# NAVIGATION_UNIT.net
KiCad netlist of a schematic drawn in Altium Designer
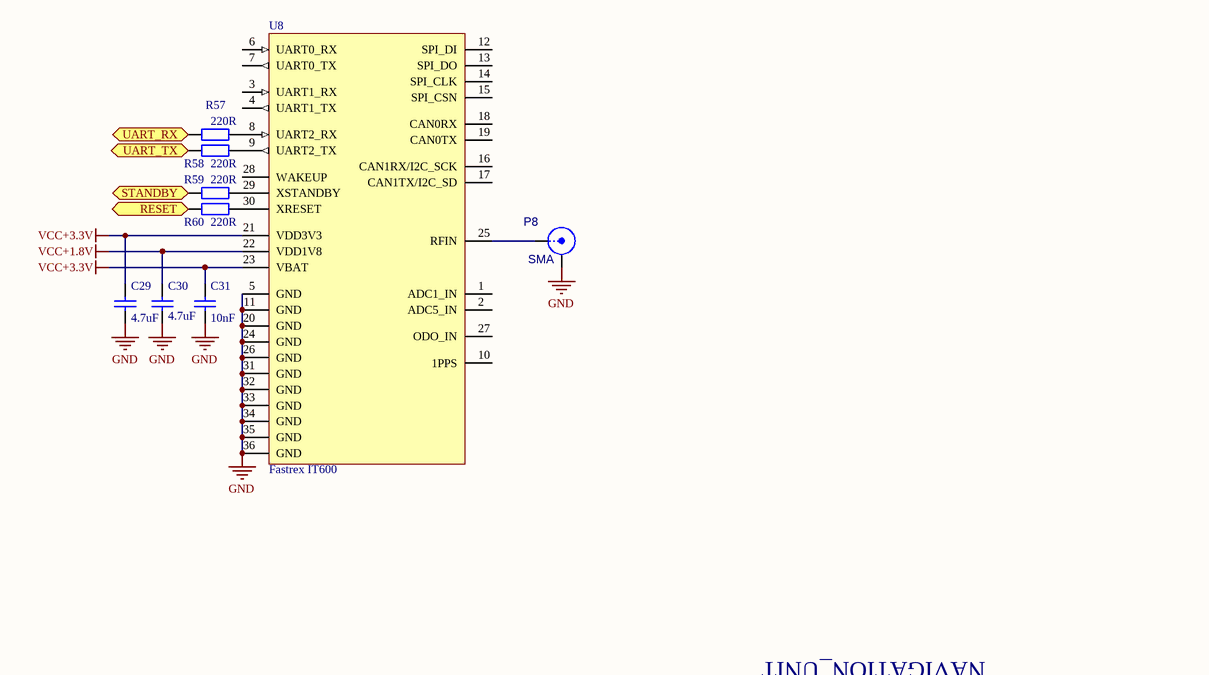
[diagram p0: NAVIGATION_UNIT.SchDoc]

(export (version "E")
  (design (tool "Eeschema 10.0.6"))
  (components
    (comp (ref "C29")
      (value "4.7uF")
      (footprint "C0805")
      (description "Capasitor_SMD_0808/")
      (fields (field (name "Comment") "0805"))
      (libsource (lib "NEW") (part "Capasitor_SMD_0805"))
    )
    (comp (ref "C30")
      (value "4.7uF")
      (footprint "C0805")
      (description "Capasitor_SMD_0808/")
      (fields (field (name "Comment") "0805"))
      (libsource (lib "NEW") (part "Capasitor_SMD_0805"))
    )
    (comp (ref "C31")
      (value "10nF")
      (footprint "C0603")
      (description "Capasitor_SMD_0808/")
      (fields (field (name "Comment") "0805"))
      (libsource (lib "NEW") (part "Capasitor_SMD_0805"))
    )
    (comp (ref "P8")
      (value "SMA")
      (footprint "SMA")
      (fields (field (name "PUBLISHER") "Altium Limited"))
      (libsource (lib "NEW") (part "SMA"))
    )
    (comp (ref "R57")
      (value "220R")
      (footprint "C0603")
      (description "Resistor")
      (fields (field (name "Comment") "RES"))
      (libsource (lib "NEW") (part "RES"))
    )
    (comp (ref "R58")
      (value "220R")
      (footprint "C0603")
      (description "Resistor")
      (fields (field (name "Comment") "RES"))
      (libsource (lib "NEW") (part "RES"))
    )
    (comp (ref "R59")
      (value "220R")
      (footprint "C0603")
      (description "Resistor")
      (fields (field (name "Comment") "RES"))
      (libsource (lib "NEW") (part "RES"))
    )
    (comp (ref "R60")
      (value "220R")
      (footprint "C0603")
      (description "Resistor")
      (fields (field (name "Comment") "RES"))
      (libsource (lib "NEW") (part "RES"))
    )
    (comp (ref "U8")
      (value "Fastrex IT600")
      (footprint "Fastrex_IT600")
      (description "GPS/ГЛОНАСС")
      (libsource (lib "NEW") (part "Fastrax IT600"))
    )
  )
  (nets
    (net (code "1") (name "/RESET") (class "Default")
      (node (ref "R60") (pin "1") (pinfunction "1_1") (pintype "passive"))
    )
    (net (code "2") (name "/STANDBY") (class "Default")
      (node (ref "R59") (pin "1") (pinfunction "1_1") (pintype "passive"))
    )
    (net (code "3") (name "/UART_RX") (class "Default")
      (node (ref "R57") (pin "1") (pinfunction "1_1") (pintype "passive"))
    )
    (net (code "4") (name "/UART_TX") (class "Default")
      (node (ref "R58") (pin "1") (pinfunction "1_1") (pintype "passive"))
    )
    (net (code "5") (name "GND") (class "Default")
      (node (ref "C29") (pin "2") (pinfunction "2_2") (pintype "passive"))
      (node (ref "C30") (pin "2") (pinfunction "2_2") (pintype "passive"))
      (node (ref "C31") (pin "2") (pinfunction "2_2") (pintype "passive"))
      (node (ref "P8") (pin "2") (pinfunction "Y_2") (pintype "passive"))
      (node (ref "U8") (pin "11") (pinfunction "GND_11") (pintype "passive"))
      (node (ref "U8") (pin "20") (pinfunction "GND_20") (pintype "passive"))
      (node (ref "U8") (pin "24") (pinfunction "GND_24") (pintype "passive"))
      (node (ref "U8") (pin "26") (pinfunction "GND_26") (pintype "passive"))
      (node (ref "U8") (pin "31") (pinfunction "GND_31") (pintype "passive"))
      (node (ref "U8") (pin "32") (pinfunction "GND_32") (pintype "passive"))
      (node (ref "U8") (pin "33") (pinfunction "GND_33") (pintype "passive"))
      (node (ref "U8") (pin "34") (pinfunction "GND_34") (pintype "passive"))
      (node (ref "U8") (pin "35") (pinfunction "GND_35") (pintype "passive"))
      (node (ref "U8") (pin "36") (pinfunction "GND_36") (pintype "passive"))
      (node (ref "U8") (pin "5") (pinfunction "GND_5") (pintype "passive"))
    )
    (net (code "6") (name "Net-(P8-X)") (class "Default")
      (node (ref "P8") (pin "1") (pinfunction "X_1") (pintype "passive"))
      (node (ref "U8") (pin "25") (pinfunction "RFIN_25") (pintype "passive"))
    )
    (net (code "7") (name "Net-(U8-UART2_RX)") (class "Default")
      (node (ref "R57") (pin "2") (pinfunction "2_2") (pintype "passive"))
      (node (ref "U8") (pin "8") (pinfunction "UART2_RX_8") (pintype "input"))
    )
    (net (code "8") (name "Net-(U8-UART2_TX)") (class "Default")
      (node (ref "R58") (pin "2") (pinfunction "2_2") (pintype "passive"))
      (node (ref "U8") (pin "9") (pinfunction "UART2_TX_9") (pintype "output"))
    )
    (net (code "9") (name "Net-(U8-XRESET)") (class "Default")
      (node (ref "R60") (pin "2") (pinfunction "2_2") (pintype "passive"))
      (node (ref "U8") (pin "30") (pinfunction "XRESET_30") (pintype "passive"))
    )
    (net (code "10") (name "Net-(U8-XSTANDBY)") (class "Default")
      (node (ref "R59") (pin "2") (pinfunction "2_2") (pintype "passive"))
      (node (ref "U8") (pin "29") (pinfunction "XSTANDBY_29") (pintype "passive"))
    )
    (net (code "11") (name "VCC+1.8V") (class "Default")
      (node (ref "C30") (pin "1") (pinfunction "1_1") (pintype "passive"))
      (node (ref "U8") (pin "22") (pinfunction "VDD1V8_22") (pintype "passive"))
    )
    (net (code "12") (name "VCC+3.3V") (class "Default")
      (node (ref "C29") (pin "1") (pinfunction "1_1") (pintype "passive"))
      (node (ref "C31") (pin "1") (pinfunction "1_1") (pintype "passive"))
      (node (ref "U8") (pin "21") (pinfunction "VDD3V3_21") (pintype "passive"))
      (node (ref "U8") (pin "23") (pinfunction "VBAT_23") (pintype "passive"))
    )
    (net (code "13") (name "unconnected-(U8-1PPS-Pad10)") (class "Default")
      (node (ref "U8") (pin "10") (pinfunction "1PPS_10") (pintype "passive"))
    )
    (net (code "14") (name "unconnected-(U8-ADC1_IN-Pad1)") (class "Default")
      (node (ref "U8") (pin "1") (pinfunction "ADC1_IN_1") (pintype "passive"))
    )
    (net (code "15") (name "unconnected-(U8-ADC5_IN-Pad2)") (class "Default")
      (node (ref "U8") (pin "2") (pinfunction "ADC5_IN_2") (pintype "passive"))
    )
    (net (code "16") (name "unconnected-(U8-CAN0RX-Pad18)") (class "Default")
      (node (ref "U8") (pin "18") (pinfunction "CAN0RX_18") (pintype "passive"))
    )
    (net (code "17") (name "unconnected-(U8-CAN0TX-Pad19)") (class "Default")
      (node (ref "U8") (pin "19") (pinfunction "CAN0TX_19") (pintype "passive"))
    )
    (net (code "18") (name "unconnected-(U8-CAN1RX{slash}I2C_SCK-Pad16)") (class "Default")
      (node (ref "U8") (pin "16") (pinfunction "CAN1RX/I2C_SCK_16") (pintype "passive"))
    )
    (net (code "19") (name "unconnected-(U8-CAN1TX{slash}I2C_SD-Pad17)") (class "Default")
      (node (ref "U8") (pin "17") (pinfunction "CAN1TX/I2C_SD_17") (pintype "passive"))
    )
    (net (code "20") (name "unconnected-(U8-ODO_IN-Pad27)") (class "Default")
      (node (ref "U8") (pin "27") (pinfunction "ODO_IN_27") (pintype "passive"))
    )
    (net (code "21") (name "unconnected-(U8-SPI_CLK-Pad14)") (class "Default")
      (node (ref "U8") (pin "14") (pinfunction "SPI_CLK_14") (pintype "passive"))
    )
    (net (code "22") (name "unconnected-(U8-SPI_CSN-Pad15)") (class "Default")
      (node (ref "U8") (pin "15") (pinfunction "SPI_CSN_15") (pintype "passive"))
    )
    (net (code "23") (name "unconnected-(U8-SPI_DI-Pad12)") (class "Default")
      (node (ref "U8") (pin "12") (pinfunction "SPI_DI_12") (pintype "passive"))
    )
    (net (code "24") (name "unconnected-(U8-SPI_DO-Pad13)") (class "Default")
      (node (ref "U8") (pin "13") (pinfunction "SPI_DO_13") (pintype "passive"))
    )
    (net (code "25") (name "unconnected-(U8-UART0_RX-Pad6)") (class "Default")
      (node (ref "U8") (pin "6") (pinfunction "UART0_RX_6") (pintype "input"))
    )
    (net (code "26") (name "unconnected-(U8-UART0_TX-Pad7)") (class "Default")
      (node (ref "U8") (pin "7") (pinfunction "UART0_TX_7") (pintype "output"))
    )
    (net (code "27") (name "unconnected-(U8-UART1_RX-Pad3)") (class "Default")
      (node (ref "U8") (pin "3") (pinfunction "UART1_RX_3") (pintype "input"))
    )
    (net (code "28") (name "unconnected-(U8-UART1_TX-Pad4)") (class "Default")
      (node (ref "U8") (pin "4") (pinfunction "UART1_TX_4") (pintype "output"))
    )
    (net (code "29") (name "unconnected-(U8-WAKEUP-Pad28)") (class "Default")
      (node (ref "U8") (pin "28") (pinfunction "WAKEUP_28") (pintype "passive"))
    )
  )
)
